# e75-2g4m10s.net
KiCad netlist of a schematic drawn in EAGLE
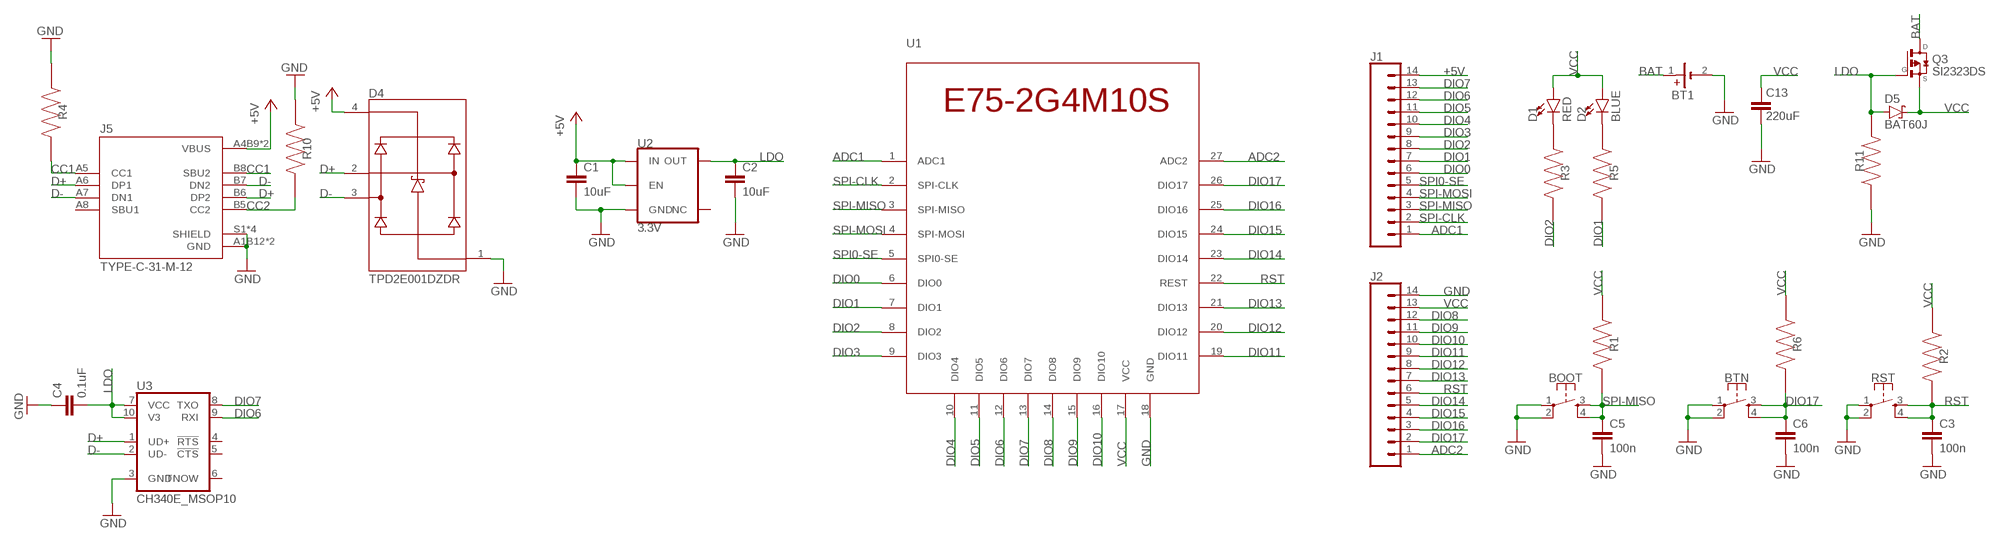
[diagram p0: schematic, sheet 1]

(export (version "E")
  (design (tool "Eeschema 10.0.6"))
  (components
    (comp (ref "BOOT")
      (value "MOMENTARY-SWITCH-SPST-2-SMD-4.6X2.8MM")
      (footprint "eagle-import:TACTILE_SWITCH_SMD_4.6X2.8MM")
      (libsource (lib "eagle-import") (part "MOMENTARY-SWITCH-SPST-2-SMD-4.6X2.8MM"))
    )
    (comp (ref "BT1")
      (value "79527141")
      (footprint "eagle-import:79527141")
      (fields
        (field (name "DIGIKEY_PART_NO") "732-12325-2-ND")
        (field (name "MANUFACTURER") "Wurth Electronics Inc.")
        (field (name "CREATED_BY") "PCBLayout.com")
      )
      (libsource (lib "eagle-import") (part "79527141"))
    )
    (comp (ref "BTN")
      (value "MOMENTARY-SWITCH-SPST-2-SMD-4.6X2.8MM")
      (footprint "eagle-import:TACTILE_SWITCH_SMD_4.6X2.8MM")
      (libsource (lib "eagle-import") (part "MOMENTARY-SWITCH-SPST-2-SMD-4.6X2.8MM"))
    )
    (comp (ref "C1")
      (value "10uF")
      (footprint "eagle-import:0603")
      (libsource (lib "eagle-import") (part "10UF-0603-6.3V-20%"))
    )
    (comp (ref "C2")
      (value "10uF")
      (footprint "eagle-import:0603")
      (libsource (lib "eagle-import") (part "10UF-0603-6.3V-20%"))
    )
    (comp (ref "C3")
      (value "100n")
      (footprint "eagle-import:0603")
      (libsource (lib "eagle-import") (part "SparkFun-Capacitors_510_0.1UF-0603-25V-5%"))
    )
    (comp (ref "C4")
      (value "0.1uF")
      (footprint "eagle-import:0603")
      (libsource (lib "eagle-import") (part "0.1UF-0603-25V-(+80/-20%)"))
    )
    (comp (ref "C5")
      (value "100n")
      (footprint "eagle-import:0603")
      (libsource (lib "eagle-import") (part "SparkFun-Capacitors_510_0.1UF-0603-25V-5%"))
    )
    (comp (ref "C6")
      (value "100n")
      (footprint "eagle-import:0603")
      (libsource (lib "eagle-import") (part "SparkFun-Capacitors_510_0.1UF-0603-25V-5%"))
    )
    (comp (ref "C13")
      (value "220uF")
      (footprint "eagle-import:CAPM7343X310")
      (libsource (lib "eagle-import") (part "CTANTALUM-2917(7343-METRIC)_"))
    )
    (comp (ref "D1")
      (value "RED")
      (footprint "eagle-import:LED-0603")
      (libsource (lib "eagle-import") (part "LED-RED0603"))
    )
    (comp (ref "D2")
      (value "BLUE")
      (footprint "eagle-import:LED-0603")
      (libsource (lib "eagle-import") (part "LED-GREEN0603"))
    )
    (comp (ref "D4")
      (value "TPD2E001DZDR")
      (footprint "eagle-import:SOT192P237X122-4N")
      (fields (field (name "MF") "Texas Instruments"))
      (libsource (lib "eagle-import") (part "TPD2E001DZDR"))
    )
    (comp (ref "D5")
      (value "BAT60J")
      (footprint "eagle-import:SOD323_ST")
      (libsource (lib "eagle-import") (part "BAT60J"))
    )
    (comp (ref "J1")
      (value "CONN_14NO_SILK")
      (footprint "eagle-import:1X14_NO_SILK")
      (libsource (lib "eagle-import") (part "CONN_14NO_SILK"))
    )
    (comp (ref "J2")
      (value "CONN_14NO_SILK")
      (footprint "eagle-import:1X14_NO_SILK")
      (libsource (lib "eagle-import") (part "CONN_14NO_SILK"))
    )
    (comp (ref "J5")
      (value "TYPE-C-31-M-12")
      (footprint "eagle-import:HRO_TYPE-C-31-M-12")
      (fields (field (name "MF") "HRO Electronics Co., Ltd."))
      (libsource (lib "eagle-import") (part "TYPE-C-31-M-12"))
    )
    (comp (ref "Q3")
      (value "SI2323DS")
      (footprint "eagle-import:SOT23")
      (fields (field (name "MF") "Vishay Siliconix"))
      (libsource (lib "eagle-import") (part "SI2323DS"))
    )
    (comp (ref "R1")
      (value "10k")
      (footprint "eagle-import:RESC1005X40N")
      (fields (field (name "MF") "Yageo") (field (name "MP") "RC0402FR-073M6L"))
      (libsource (lib "eagle-import") (part "RC0402FR-073M6L"))
    )
    (comp (ref "R2")
      (value "10k")
      (footprint "eagle-import:RESC1005X40N")
      (fields (field (name "MF") "Yageo") (field (name "MP") "RC0402FR-073M6L"))
      (libsource (lib "eagle-import") (part "RC0402FR-073M6L"))
    )
    (comp (ref "R3")
      (value "2k")
      (footprint "eagle-import:RESC1005X40N")
      (fields (field (name "MF") "Yageo") (field (name "MP") "RC0402FR-073M6L"))
      (libsource (lib "eagle-import") (part "RC0402FR-073M6L"))
    )
    (comp (ref "R4")
      (value "5.1k")
      (footprint "eagle-import:RESC1005X40N")
      (fields (field (name "MF") "Yageo") (field (name "MP") "RC0402FR-073M6L"))
      (libsource (lib "eagle-import") (part "RC0402FR-073M6L"))
    )
    (comp (ref "R5")
      (value "2k")
      (footprint "eagle-import:RESC1005X40N")
      (fields (field (name "MF") "Yageo") (field (name "MP") "RC0402FR-073M6L"))
      (libsource (lib "eagle-import") (part "RC0402FR-073M6L"))
    )
    (comp (ref "R6")
      (value "10k")
      (footprint "eagle-import:RESC1005X40N")
      (fields (field (name "MF") "Yageo") (field (name "MP") "RC0402FR-073M6L"))
      (libsource (lib "eagle-import") (part "RC0402FR-073M6L"))
    )
    (comp (ref "R10")
      (value "5.1k")
      (footprint "eagle-import:RESC1005X40N")
      (fields (field (name "MF") "Yageo") (field (name "MP") "RC0402FR-073M6L"))
      (libsource (lib "eagle-import") (part "RC0402FR-073M6L"))
    )
    (comp (ref "R11")
      (value "10k")
      (footprint "eagle-import:RESC1005X40N")
      (fields (field (name "MF") "Yageo") (field (name "MP") "RC0402FR-073M6L"))
      (libsource (lib "eagle-import") (part "RC0402FR-073M6L"))
    )
    (comp (ref "RST")
      (value "MOMENTARY-SWITCH-SPST-2-SMD-4.6X2.8MM")
      (footprint "eagle-import:TACTILE_SWITCH_SMD_4.6X2.8MM")
      (libsource (lib "eagle-import") (part "MOMENTARY-SWITCH-SPST-2-SMD-4.6X2.8MM"))
    )
    (comp (ref "U1")
      (value "E73-2G4M04S1BE75-2G4M10S")
      (footprint "eagle-import:E75-2G4M10S")
      (libsource (lib "eagle-import") (part "E73-2G4M04S1BE75-2G4M10S"))
    )
    (comp (ref "U2")
      (value "3.3V")
      (footprint "eagle-import:SOT23-5")
      (libsource (lib "eagle-import") (part "V_REG_AP2112K-3.3V"))
    )
    (comp (ref "U3")
      (value "CH340E_MSOP10")
      (footprint "eagle-import:MSOP10")
      (fields (field (name "MF") "WCH") (field (name "MP") "CH340E"))
      (libsource (lib "eagle-import") (part "CH340E_MSOP10"))
    )
  )
  (nets
    (net (code "1") (name "+5V") (class "Default")
      (node (ref "C1") (pin "1") (pinfunction "1_1") (pintype "passive"))
      (node (ref "D4") (pin "4") (pinfunction "VCC_4") (pintype "power_in"))
      (node (ref "J1") (pin "14") (pinfunction "14_14") (pintype "passive"))
      (node (ref "J5") (pin "A4B9") (pinfunction "VBUS_A4B9") (pintype "power_in"))
      (node (ref "J5") (pin "B4A9") (pinfunction "VBUS_B4A9") (pintype "power_in"))
      (node (ref "U2") (pin "1") (pinfunction "IN_1") (pintype "input"))
      (node (ref "U2") (pin "3") (pinfunction "EN_3") (pintype "input"))
    )
    (net (code "2") (name "/ADC1") (class "Default")
      (node (ref "J1") (pin "1") (pinfunction "1_1") (pintype "passive"))
      (node (ref "U1") (pin "1") (pinfunction "ADC1_1") (pintype "bidirectional"))
    )
    (net (code "3") (name "/ADC2") (class "Default")
      (node (ref "J2") (pin "1") (pinfunction "1_1") (pintype "passive"))
      (node (ref "U1") (pin "27") (pinfunction "ADC2_27") (pintype "bidirectional"))
    )
    (net (code "4") (name "/BAT") (class "Default")
      (node (ref "BT1") (pin "1") (pinfunction "+_1") (pintype "passive"))
      (node (ref "Q3") (pin "3") (pinfunction "D_3") (pintype "passive"))
    )
    (net (code "5") (name "/CC1") (class "Default")
      (node (ref "J5") (pin "A5") (pinfunction "CC1_A5") (pintype "bidirectional"))
      (node (ref "J5") (pin "B8") (pinfunction "SBU2_B8") (pintype "bidirectional"))
      (node (ref "R4") (pin "2") (pinfunction "2_2") (pintype "passive"))
    )
    (net (code "6") (name "/CC2") (class "Default")
      (node (ref "J5") (pin "B5") (pinfunction "CC2_B5") (pintype "bidirectional"))
      (node (ref "R10") (pin "2") (pinfunction "2_2") (pintype "passive"))
    )
    (net (code "7") (name "/D+") (class "Default")
      (node (ref "D4") (pin "2") (pinfunction "IO1_2") (pintype "bidirectional"))
      (node (ref "J5") (pin "A6") (pinfunction "DP1_A6") (pintype "bidirectional"))
      (node (ref "J5") (pin "B6") (pinfunction "DP2_B6") (pintype "bidirectional"))
      (node (ref "U3") (pin "1") (pinfunction "UD+_1") (pintype "bidirectional"))
    )
    (net (code "8") (name "/D-") (class "Default")
      (node (ref "D4") (pin "3") (pinfunction "IO2_3") (pintype "bidirectional"))
      (node (ref "J5") (pin "A7") (pinfunction "DN1_A7") (pintype "bidirectional"))
      (node (ref "J5") (pin "B7") (pinfunction "DN2_B7") (pintype "bidirectional"))
      (node (ref "U3") (pin "2") (pinfunction "UD-_2") (pintype "bidirectional"))
    )
    (net (code "9") (name "/DIO0") (class "Default")
      (node (ref "J1") (pin "6") (pinfunction "6_6") (pintype "passive"))
      (node (ref "U1") (pin "6") (pinfunction "DIO0_6") (pintype "bidirectional"))
    )
    (net (code "10") (name "/DIO1") (class "Default")
      (node (ref "J1") (pin "7") (pinfunction "7_7") (pintype "passive"))
      (node (ref "R5") (pin "2") (pinfunction "2_2") (pintype "passive"))
      (node (ref "U1") (pin "7") (pinfunction "DIO1_7") (pintype "bidirectional"))
    )
    (net (code "11") (name "/DIO2") (class "Default")
      (node (ref "J1") (pin "8") (pinfunction "8_8") (pintype "passive"))
      (node (ref "R3") (pin "2") (pinfunction "2_2") (pintype "passive"))
      (node (ref "U1") (pin "8") (pinfunction "DIO2_8") (pintype "bidirectional"))
    )
    (net (code "12") (name "/DIO3") (class "Default")
      (node (ref "J1") (pin "9") (pinfunction "9_9") (pintype "passive"))
      (node (ref "U1") (pin "9") (pinfunction "DIO3_9") (pintype "bidirectional"))
    )
    (net (code "13") (name "/DIO4") (class "Default")
      (node (ref "J1") (pin "10") (pinfunction "10_10") (pintype "passive"))
      (node (ref "U1") (pin "10") (pinfunction "DIO4_10") (pintype "bidirectional"))
    )
    (net (code "14") (name "/DIO5") (class "Default")
      (node (ref "J1") (pin "11") (pinfunction "11_11") (pintype "passive"))
      (node (ref "U1") (pin "11") (pinfunction "DIO5_11") (pintype "bidirectional"))
    )
    (net (code "15") (name "/DIO6") (class "Default")
      (node (ref "J1") (pin "12") (pinfunction "12_12") (pintype "passive"))
      (node (ref "U1") (pin "12") (pinfunction "DIO6_12") (pintype "bidirectional"))
      (node (ref "U3") (pin "9") (pinfunction "RXI_9") (pintype "bidirectional"))
    )
    (net (code "16") (name "/DIO7") (class "Default")
      (node (ref "J1") (pin "13") (pinfunction "13_13") (pintype "passive"))
      (node (ref "U1") (pin "13") (pinfunction "DIO7_13") (pintype "bidirectional"))
      (node (ref "U3") (pin "8") (pinfunction "TXO_8") (pintype "bidirectional"))
    )
    (net (code "17") (name "/DIO8") (class "Default")
      (node (ref "J2") (pin "12") (pinfunction "12_12") (pintype "passive"))
      (node (ref "U1") (pin "14") (pinfunction "DIO8_14") (pintype "bidirectional"))
    )
    (net (code "18") (name "/DIO9") (class "Default")
      (node (ref "J2") (pin "11") (pinfunction "11_11") (pintype "passive"))
      (node (ref "U1") (pin "15") (pinfunction "DIO9_15") (pintype "bidirectional"))
    )
    (net (code "19") (name "/DIO10") (class "Default")
      (node (ref "J2") (pin "10") (pinfunction "10_10") (pintype "passive"))
      (node (ref "U1") (pin "16") (pinfunction "DIO10_16") (pintype "bidirectional"))
    )
    (net (code "20") (name "/DIO11") (class "Default")
      (node (ref "J2") (pin "9") (pinfunction "9_9") (pintype "passive"))
      (node (ref "U1") (pin "19") (pinfunction "DIO11_19") (pintype "bidirectional"))
    )
    (net (code "21") (name "/DIO12") (class "Default")
      (node (ref "J2") (pin "8") (pinfunction "8_8") (pintype "passive"))
      (node (ref "U1") (pin "20") (pinfunction "DIO12_20") (pintype "bidirectional"))
    )
    (net (code "22") (name "/DIO13") (class "Default")
      (node (ref "J2") (pin "7") (pinfunction "7_7") (pintype "passive"))
      (node (ref "U1") (pin "21") (pinfunction "DIO13_21") (pintype "bidirectional"))
    )
    (net (code "23") (name "/DIO14") (class "Default")
      (node (ref "J2") (pin "5") (pinfunction "5_5") (pintype "passive"))
      (node (ref "U1") (pin "23") (pinfunction "DIO14_23") (pintype "bidirectional"))
    )
    (net (code "24") (name "/DIO15") (class "Default")
      (node (ref "J2") (pin "4") (pinfunction "4_4") (pintype "passive"))
      (node (ref "U1") (pin "24") (pinfunction "DIO15_24") (pintype "bidirectional"))
    )
    (net (code "25") (name "/DIO16") (class "Default")
      (node (ref "J2") (pin "3") (pinfunction "3_3") (pintype "passive"))
      (node (ref "U1") (pin "25") (pinfunction "DIO16_25") (pintype "bidirectional"))
    )
    (net (code "26") (name "/DIO17") (class "Default")
      (node (ref "BTN") (pin "3") (pinfunction "3_3") (pintype "passive"))
      (node (ref "BTN") (pin "4") (pinfunction "4_4") (pintype "passive"))
      (node (ref "C6") (pin "1") (pinfunction "1_1") (pintype "passive"))
      (node (ref "J2") (pin "2") (pinfunction "2_2") (pintype "passive"))
      (node (ref "R6") (pin "2") (pinfunction "2_2") (pintype "passive"))
      (node (ref "U1") (pin "26") (pinfunction "DIO17_26") (pintype "bidirectional"))
    )
    (net (code "27") (name "/LDO") (class "Default")
      (node (ref "C2") (pin "1") (pinfunction "1_1") (pintype "passive"))
      (node (ref "C4") (pin "2") (pinfunction "2_2") (pintype "passive"))
      (node (ref "D5") (pin "A") (pinfunction "A_A") (pintype "passive"))
      (node (ref "Q3") (pin "1") (pinfunction "G_1") (pintype "passive"))
      (node (ref "R11") (pin "2") (pinfunction "2_2") (pintype "passive"))
      (node (ref "U2") (pin "5") (pinfunction "OUT_5") (pintype "passive"))
      (node (ref "U3") (pin "10") (pinfunction "V3_10") (pintype "bidirectional"))
      (node (ref "U3") (pin "7") (pinfunction "VCC_7") (pintype "bidirectional"))
    )
    (net (code "28") (name "/RST") (class "Default")
      (node (ref "C3") (pin "1") (pinfunction "1_1") (pintype "passive"))
      (node (ref "J2") (pin "6") (pinfunction "6_6") (pintype "passive"))
      (node (ref "R2") (pin "2") (pinfunction "2_2") (pintype "passive"))
      (node (ref "RST") (pin "3") (pinfunction "3_3") (pintype "passive"))
      (node (ref "RST") (pin "4") (pinfunction "4_4") (pintype "passive"))
      (node (ref "U1") (pin "22") (pinfunction "REST_22") (pintype "bidirectional"))
    )
    (net (code "29") (name "/SPI-CLK") (class "Default")
      (node (ref "J1") (pin "2") (pinfunction "2_2") (pintype "passive"))
      (node (ref "U1") (pin "2") (pinfunction "SPI-CLK_2") (pintype "bidirectional"))
    )
    (net (code "30") (name "/SPI-MISO") (class "Default")
      (node (ref "BOOT") (pin "3") (pinfunction "3_3") (pintype "passive"))
      (node (ref "BOOT") (pin "4") (pinfunction "4_4") (pintype "passive"))
      (node (ref "C5") (pin "1") (pinfunction "1_1") (pintype "passive"))
      (node (ref "J1") (pin "3") (pinfunction "3_3") (pintype "passive"))
      (node (ref "R1") (pin "2") (pinfunction "2_2") (pintype "passive"))
      (node (ref "U1") (pin "3") (pinfunction "SPI-MISO_3") (pintype "bidirectional"))
    )
    (net (code "31") (name "/SPI-MOSI") (class "Default")
      (node (ref "J1") (pin "4") (pinfunction "4_4") (pintype "passive"))
      (node (ref "U1") (pin "4") (pinfunction "SPI-MOSI_4") (pintype "bidirectional"))
    )
    (net (code "32") (name "/SPI0-SE") (class "Default")
      (node (ref "J1") (pin "5") (pinfunction "5_5") (pintype "passive"))
      (node (ref "U1") (pin "5") (pinfunction "SPI0-SE_5") (pintype "bidirectional"))
    )
    (net (code "33") (name "/VCC") (class "Default")
      (node (ref "C13") (pin "1") (pinfunction "1_1") (pintype "passive"))
      (node (ref "D1") (pin "A") (pinfunction "A_A") (pintype "passive"))
      (node (ref "D2") (pin "A") (pinfunction "A_A") (pintype "passive"))
      (node (ref "D5") (pin "C") (pinfunction "C_C") (pintype "passive"))
      (node (ref "J2") (pin "13") (pinfunction "13_13") (pintype "passive"))
      (node (ref "Q3") (pin "2") (pinfunction "S_2") (pintype "passive"))
      (node (ref "R1") (pin "1") (pinfunction "1_1") (pintype "passive"))
      (node (ref "R2") (pin "1") (pinfunction "1_1") (pintype "passive"))
      (node (ref "R6") (pin "1") (pinfunction "1_1") (pintype "passive"))
      (node (ref "U1") (pin "17") (pinfunction "VCC_17") (pintype "bidirectional"))
    )
    (net (code "34") (name "GND") (class "Default")
      (node (ref "BOOT") (pin "1") (pinfunction "1_1") (pintype "passive"))
      (node (ref "BOOT") (pin "2") (pinfunction "2_2") (pintype "passive"))
      (node (ref "BT1") (pin "2") (pinfunction "-_2") (pintype "passive"))
      (node (ref "BTN") (pin "1") (pinfunction "1_1") (pintype "passive"))
      (node (ref "BTN") (pin "2") (pinfunction "2_2") (pintype "passive"))
      (node (ref "C1") (pin "2") (pinfunction "2_2") (pintype "passive"))
      (node (ref "C13") (pin "2") (pinfunction "2_2") (pintype "passive"))
      (node (ref "C2") (pin "2") (pinfunction "2_2") (pintype "passive"))
      (node (ref "C3") (pin "2") (pinfunction "2_2") (pintype "passive"))
      (node (ref "C4") (pin "1") (pinfunction "1_1") (pintype "passive"))
      (node (ref "C5") (pin "2") (pinfunction "2_2") (pintype "passive"))
      (node (ref "C6") (pin "2") (pinfunction "2_2") (pintype "passive"))
      (node (ref "D4") (pin "1") (pinfunction "GND_1") (pintype "power_in"))
      (node (ref "J2") (pin "14") (pinfunction "14_14") (pintype "passive"))
      (node (ref "J5") (pin "A1B12") (pinfunction "GND_A1B12") (pintype "power_in"))
      (node (ref "J5") (pin "B1A12") (pinfunction "GND_B1A12") (pintype "power_in"))
      (node (ref "J5") (pin "S1") (pinfunction "SHIELD_S1") (pintype "passive"))
      (node (ref "J5") (pin "S2") (pinfunction "SHIELD_S2") (pintype "passive"))
      (node (ref "J5") (pin "S3") (pinfunction "SHIELD_S3") (pintype "passive"))
      (node (ref "J5") (pin "S4") (pinfunction "SHIELD_S4") (pintype "passive"))
      (node (ref "R10") (pin "1") (pinfunction "1_1") (pintype "passive"))
      (node (ref "R11") (pin "1") (pinfunction "1_1") (pintype "passive"))
      (node (ref "R4") (pin "1") (pinfunction "1_1") (pintype "passive"))
      (node (ref "RST") (pin "1") (pinfunction "1_1") (pintype "passive"))
      (node (ref "RST") (pin "2") (pinfunction "2_2") (pintype "passive"))
      (node (ref "U1") (pin "18") (pinfunction "GND_18") (pintype "bidirectional"))
      (node (ref "U2") (pin "2") (pinfunction "GND_2") (pintype "input"))
      (node (ref "U3") (pin "3") (pinfunction "GND_3") (pintype "bidirectional"))
    )
    (net (code "35") (name "Net-(D1-PadC)") (class "Default")
      (node (ref "D1") (pin "C") (pinfunction "C_C") (pintype "passive"))
      (node (ref "R3") (pin "1") (pinfunction "1_1") (pintype "passive"))
    )
    (net (code "36") (name "Net-(D2-PadC)") (class "Default")
      (node (ref "D2") (pin "C") (pinfunction "C_C") (pintype "passive"))
      (node (ref "R5") (pin "1") (pinfunction "1_1") (pintype "passive"))
    )
    (net (code "37") (name "unconnected-(J5-SBU1-PadA8)") (class "Default")
      (node (ref "J5") (pin "A8") (pinfunction "SBU1_A8") (pintype "bidirectional"))
    )
    (net (code "38") (name "unconnected-(U2-NC-Pad4)") (class "Default")
      (node (ref "U2") (pin "4") (pinfunction "NC_4") (pintype "no_connect"))
    )
    (net (code "39") (name "unconnected-(U3-TNOW-Pad6)") (class "Default")
      (node (ref "U3") (pin "6") (pinfunction "TNOW_6") (pintype "bidirectional"))
    )
    (net (code "40") (name "unconnected-(U3-~{CTS}-Pad5)") (class "Default")
      (node (ref "U3") (pin "5") (pinfunction "~{CTS}_5") (pintype "bidirectional"))
    )
    (net (code "41") (name "unconnected-(U3-~{RTS}-Pad4)") (class "Default")
      (node (ref "U3") (pin "4") (pinfunction "~{RTS}_4") (pintype "bidirectional"))
    )
  )
)
